# compact.net
KiCad netlist of a schematic drawn in EAGLE
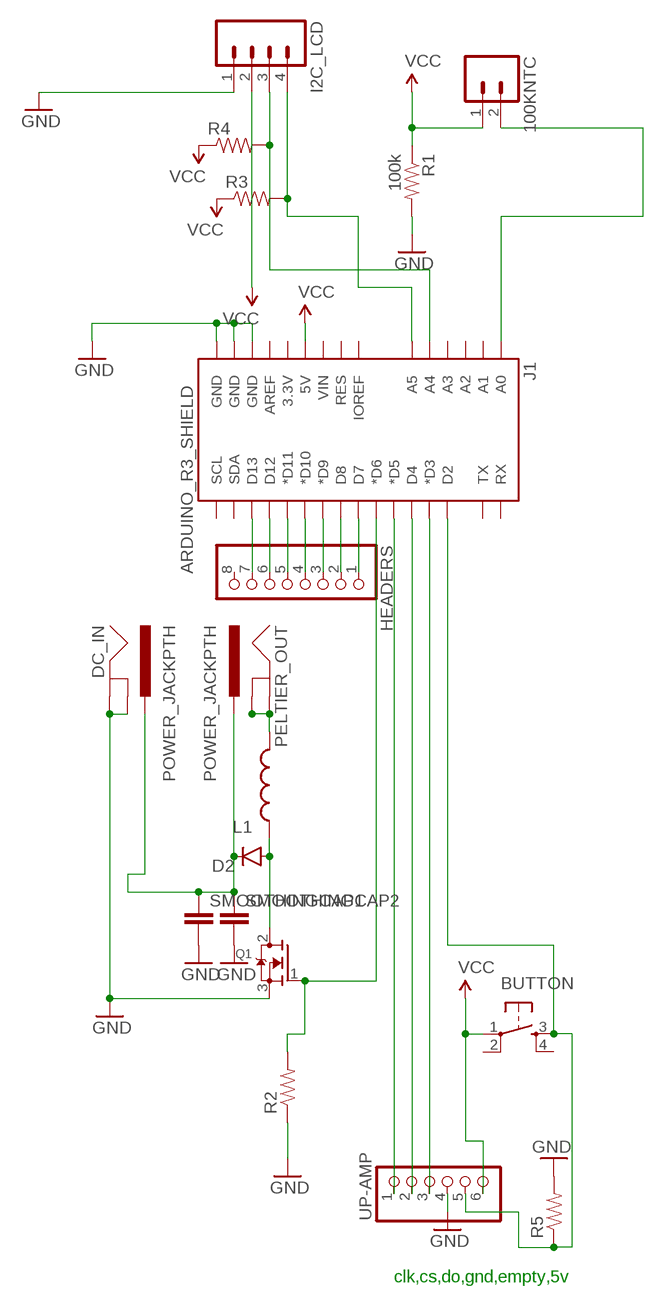
[diagram p0: schematic, sheet 1]

(export (version "E")
  (design (tool "Eeschema 10.0.6"))
  (components
    (comp (ref "100KNTC")
      (value "M02LOCK")
      (footprint "eagle-import:1X02_LOCK")
      (libsource (lib "eagle-import") (part "M02LOCK"))
    )
    (comp (ref "BUTTON")
      (value "TAC_SWITCHPTH")
      (footprint "eagle-import:TACTILE-PTH")
      (libsource (lib "eagle-import") (part "TAC_SWITCHPTH"))
    )
    (comp (ref "D2")
      (value "DIODEPTH")
      (footprint "eagle-import:DIODE-1N4001")
      (libsource (lib "eagle-import") (part "DIODEPTH"))
    )
    (comp (ref "DC_IN")
      (value "POWER_JACKPTH")
      (footprint "eagle-import:POWER_JACK_PTH")
      (libsource (lib "eagle-import") (part "POWER_JACKPTH"))
    )
    (comp (ref "HEADERS")
      (value "PINHD-1X8BIG")
      (footprint "eagle-import:1X08-BIG")
      (libsource (lib "eagle-import") (part "PINHD-1X8BIG"))
    )
    (comp (ref "I2C_LCD")
      (value "M04JST")
      (footprint "eagle-import:1X04-1.5MM_JST")
      (libsource (lib "eagle-import") (part "M04JST"))
    )
    (comp (ref "J1")
      (value "ARDUINO_R3_SHIELD")
      (footprint "eagle-import:UNO_R3_SHIELD")
      (libsource (lib "eagle-import") (part "ARDUINO_R3_SHIELD"))
    )
    (comp (ref "L1")
      (value "INDUCTORRLB0912")
      (footprint "eagle-import:RLB0912")
      (libsource (lib "eagle-import") (part "INDUCTORRLB0912"))
    )
    (comp (ref "PELTIER_OUT")
      (value "POWER_JACKPTH")
      (footprint "eagle-import:POWER_JACK_PTH")
      (libsource (lib "eagle-import") (part "POWER_JACKPTH"))
    )
    (comp (ref "Q1")
      (value "MOSFET-NGDS_TO220V")
      (footprint "eagle-import:TO220V")
      (libsource (lib "eagle-import") (part "MOSFET-NGDS_TO220V"))
    )
    (comp (ref "R1")
      (value "100k")
      (footprint "eagle-import:AXIAL-0.4")
      (libsource (lib "eagle-import") (part "RESISTORPTH-1/4W"))
    )
    (comp (ref "R2")
      (value "RESISTORPTH-1/4W")
      (footprint "eagle-import:AXIAL-0.4")
      (libsource (lib "eagle-import") (part "RESISTORPTH-1/4W"))
    )
    (comp (ref "R3")
      (value "RESISTORPTH-1/4W")
      (footprint "eagle-import:AXIAL-0.4")
      (libsource (lib "eagle-import") (part "SparkFun-Resistors_RESISTORPTH-1/4W"))
    )
    (comp (ref "R4")
      (value "RESISTORPTH-1/4W")
      (footprint "eagle-import:AXIAL-0.4")
      (libsource (lib "eagle-import") (part "SparkFun-Resistors_RESISTORPTH-1/4W"))
    )
    (comp (ref "R5")
      (value "RESISTORPTH-1/4W")
      (footprint "eagle-import:AXIAL-0.4")
      (libsource (lib "eagle-import") (part "RESISTORPTH-1/4W"))
    )
    (comp (ref "SMOOTHINGCAP1")
      (value "CAPPTH3")
      (footprint "eagle-import:CAP-PTH-LARGE")
      (libsource (lib "eagle-import") (part "CAPPTH3"))
    )
    (comp (ref "SMOOTHINGCAP2")
      (value "CAPPTH3")
      (footprint "eagle-import:CAP-PTH-LARGE")
      (libsource (lib "eagle-import") (part "CAPPTH3"))
    )
    (comp (ref "UP-AMP")
      (value "PINHD-1X6")
      (footprint "eagle-import:1X06")
      (libsource (lib "eagle-import") (part "PINHD-1X6"))
    )
  )
  (nets
    (net (code "1") (name "GND") (class "Default")
      (node (ref "DC_IN") (pin "GND") (pinfunction "GND_GND") (pintype "bidirectional"))
      (node (ref "DC_IN") (pin "GNDBREAK") (pinfunction "GNDBREAK_GNDBREAK") (pintype "bidirectional"))
      (node (ref "I2C_LCD") (pin "1") (pinfunction "1_1") (pintype "passive"))
      (node (ref "J1") (pin "GND@0") (pinfunction "GND_GND@0") (pintype "bidirectional"))
      (node (ref "J1") (pin "GND@1") (pinfunction "GND_GND@1") (pintype "bidirectional"))
      (node (ref "J1") (pin "GND@2") (pinfunction "GND_GND@2") (pintype "bidirectional"))
      (node (ref "Q1") (pin "3") (pinfunction "S_3") (pintype "bidirectional"))
      (node (ref "R1") (pin "P$2") (pinfunction "2_P$2") (pintype "passive"))
      (node (ref "R2") (pin "P$1") (pinfunction "1_P$1") (pintype "passive"))
      (node (ref "R5") (pin "P$2") (pinfunction "2_P$2") (pintype "passive"))
      (node (ref "SMOOTHINGCAP1") (pin "2") (pinfunction "2_2") (pintype "passive"))
      (node (ref "SMOOTHINGCAP2") (pin "2") (pinfunction "2_2") (pintype "passive"))
      (node (ref "UP-AMP") (pin "4") (pinfunction "4_4") (pintype "passive"))
    )
    (net (code "2") (name "Net-(100KNTC-Pad2)") (class "Default")
      (node (ref "100KNTC") (pin "2") (pinfunction "2_2") (pintype "passive"))
      (node (ref "J1") (pin "A0") (pinfunction "A0_A0") (pintype "bidirectional"))
    )
    (net (code "3") (name "Net-(D2-PadC)") (class "Default")
      (node (ref "D2") (pin "C") (pinfunction "C_C") (pintype "passive"))
      (node (ref "DC_IN") (pin "PWR") (pinfunction "PWR_PWR") (pintype "bidirectional"))
      (node (ref "PELTIER_OUT") (pin "PWR") (pinfunction "PWR_PWR") (pintype "bidirectional"))
      (node (ref "SMOOTHINGCAP1") (pin "1") (pinfunction "1_1") (pintype "passive"))
      (node (ref "SMOOTHINGCAP2") (pin "1") (pinfunction "1_1") (pintype "passive"))
    )
    (net (code "4") (name "Net-(HEADERS-Pad1)") (class "Default")
      (node (ref "HEADERS") (pin "1") (pinfunction "1_1") (pintype "passive"))
      (node (ref "J1") (pin "D7") (pinfunction "D7_D7") (pintype "bidirectional"))
    )
    (net (code "5") (name "Net-(HEADERS-Pad2)") (class "Default")
      (node (ref "HEADERS") (pin "2") (pinfunction "2_2") (pintype "passive"))
      (node (ref "J1") (pin "D8") (pinfunction "D8_D8") (pintype "bidirectional"))
    )
    (net (code "6") (name "Net-(HEADERS-Pad6)") (class "Default")
      (node (ref "HEADERS") (pin "6") (pinfunction "6_6") (pintype "passive"))
      (node (ref "J1") (pin "D12") (pinfunction "D12_D12") (pintype "bidirectional"))
    )
    (net (code "7") (name "Net-(HEADERS-Pad7)") (class "Default")
      (node (ref "HEADERS") (pin "7") (pinfunction "7_7") (pintype "passive"))
      (node (ref "J1") (pin "D13") (pinfunction "D13_D13") (pintype "bidirectional"))
    )
    (net (code "8") (name "Net-(J1-*D3)") (class "Default")
      (node (ref "J1") (pin "D3") (pinfunction "*D3_D3") (pintype "bidirectional"))
      (node (ref "UP-AMP") (pin "3") (pinfunction "3_3") (pintype "passive"))
    )
    (net (code "9") (name "Net-(J1-*D5)") (class "Default")
      (node (ref "J1") (pin "D5") (pinfunction "*D5_D5") (pintype "bidirectional"))
      (node (ref "UP-AMP") (pin "1") (pinfunction "1_1") (pintype "passive"))
    )
    (net (code "10") (name "Net-(J1-*D6)") (class "Default")
      (node (ref "J1") (pin "D6") (pinfunction "*D6_D6") (pintype "bidirectional"))
      (node (ref "Q1") (pin "1") (pinfunction "G_1") (pintype "bidirectional"))
      (node (ref "R2") (pin "P$2") (pinfunction "2_P$2") (pintype "passive"))
    )
    (net (code "11") (name "Net-(J1-*D9)") (class "Default")
      (node (ref "HEADERS") (pin "3") (pinfunction "3_3") (pintype "passive"))
      (node (ref "J1") (pin "D9") (pinfunction "*D9_D9") (pintype "bidirectional"))
    )
    (net (code "12") (name "Net-(J1-*D10)") (class "Default")
      (node (ref "HEADERS") (pin "4") (pinfunction "4_4") (pintype "passive"))
      (node (ref "J1") (pin "D10") (pinfunction "*D10_D10") (pintype "bidirectional"))
    )
    (net (code "13") (name "Net-(J1-*D11)") (class "Default")
      (node (ref "HEADERS") (pin "5") (pinfunction "5_5") (pintype "passive"))
      (node (ref "J1") (pin "D11") (pinfunction "*D11_D11") (pintype "bidirectional"))
    )
    (net (code "14") (name "Net-(J1-PadD4)") (class "Default")
      (node (ref "J1") (pin "D4") (pinfunction "D4_D4") (pintype "bidirectional"))
      (node (ref "UP-AMP") (pin "2") (pinfunction "2_2") (pintype "passive"))
    )
    (net (code "15") (name "Net-(L1-Pad2)") (class "Default")
      (node (ref "L1") (pin "2") (pinfunction "2_2") (pintype "passive"))
      (node (ref "PELTIER_OUT") (pin "GND") (pinfunction "GND_GND") (pintype "bidirectional"))
      (node (ref "PELTIER_OUT") (pin "GNDBREAK") (pinfunction "GNDBREAK_GNDBREAK") (pintype "bidirectional"))
    )
    (net (code "16") (name "Net-(Q1-D)") (class "Default")
      (node (ref "D2") (pin "A") (pinfunction "A_A") (pintype "passive"))
      (node (ref "L1") (pin "1") (pinfunction "1_1") (pintype "passive"))
      (node (ref "Q1") (pin "2") (pinfunction "D_2") (pintype "bidirectional"))
    )
    (net (code "17") (name "Net-(R3-2)") (class "Default")
      (node (ref "I2C_LCD") (pin "4") (pinfunction "4_4") (pintype "passive"))
      (node (ref "J1") (pin "A5") (pinfunction "A5_A5") (pintype "bidirectional"))
      (node (ref "R3") (pin "P$2") (pinfunction "2_P$2") (pintype "passive"))
    )
    (net (code "18") (name "Net-(R4-2)") (class "Default")
      (node (ref "I2C_LCD") (pin "3") (pinfunction "3_3") (pintype "passive"))
      (node (ref "J1") (pin "A4") (pinfunction "A4_A4") (pintype "bidirectional"))
      (node (ref "R4") (pin "P$2") (pinfunction "2_P$2") (pintype "passive"))
    )
    (net (code "19") (name "Net-(R5-1)") (class "Default")
      (node (ref "BUTTON") (pin "3") (pinfunction "3_3") (pintype "passive"))
      (node (ref "J1") (pin "D2") (pinfunction "D2_D2") (pintype "bidirectional"))
      (node (ref "R5") (pin "P$1") (pinfunction "1_P$1") (pintype "passive"))
      (node (ref "UP-AMP") (pin "5") (pinfunction "5_5") (pintype "passive"))
    )
    (net (code "20") (name "VCC") (class "Default")
      (node (ref "100KNTC") (pin "1") (pinfunction "1_1") (pintype "passive"))
      (node (ref "BUTTON") (pin "1") (pinfunction "1_1") (pintype "passive"))
      (node (ref "I2C_LCD") (pin "2") (pinfunction "2_2") (pintype "passive"))
      (node (ref "J1") (pin "5V") (pinfunction "5V_5V") (pintype "bidirectional"))
      (node (ref "R1") (pin "P$1") (pinfunction "1_P$1") (pintype "passive"))
      (node (ref "R3") (pin "P$1") (pinfunction "1_P$1") (pintype "passive"))
      (node (ref "R4") (pin "P$1") (pinfunction "1_P$1") (pintype "passive"))
      (node (ref "UP-AMP") (pin "6") (pinfunction "6_6") (pintype "passive"))
    )
    (net (code "21") (name "unconnected-(BUTTON-Pad2)") (class "Default")
      (node (ref "BUTTON") (pin "2") (pinfunction "2_2") (pintype "passive"))
    )
    (net (code "22") (name "unconnected-(BUTTON-Pad4)") (class "Default")
      (node (ref "BUTTON") (pin "4") (pinfunction "4_4") (pintype "passive"))
    )
    (net (code "23") (name "unconnected-(HEADERS-Pad8)") (class "Default")
      (node (ref "HEADERS") (pin "8") (pinfunction "8_8") (pintype "passive"))
    )
    (net (code "24") (name "unconnected-(J1-Pad3.3V)") (class "Default")
      (node (ref "J1") (pin "3.3V") (pinfunction "3.3V_3.3V") (pintype "bidirectional"))
    )
    (net (code "25") (name "unconnected-(J1-PadA1)") (class "Default")
      (node (ref "J1") (pin "A1") (pinfunction "A1_A1") (pintype "bidirectional"))
    )
    (net (code "26") (name "unconnected-(J1-PadA2)") (class "Default")
      (node (ref "J1") (pin "A2") (pinfunction "A2_A2") (pintype "bidirectional"))
    )
    (net (code "27") (name "unconnected-(J1-PadA3)") (class "Default")
      (node (ref "J1") (pin "A3") (pinfunction "A3_A3") (pintype "bidirectional"))
    )
    (net (code "28") (name "unconnected-(J1-PadAREF)") (class "Default")
      (node (ref "J1") (pin "AREF") (pinfunction "AREF_AREF") (pintype "bidirectional"))
    )
    (net (code "29") (name "unconnected-(J1-PadIOREF)") (class "Default")
      (node (ref "J1") (pin "IOREF") (pinfunction "IOREF_IOREF") (pintype "bidirectional"))
    )
    (net (code "30") (name "unconnected-(J1-PadRES)") (class "Default")
      (node (ref "J1") (pin "RES") (pinfunction "RES_RES") (pintype "bidirectional"))
    )
    (net (code "31") (name "unconnected-(J1-PadRX)") (class "Default")
      (node (ref "J1") (pin "RX") (pinfunction "RX_RX") (pintype "bidirectional"))
    )
    (net (code "32") (name "unconnected-(J1-PadSCL)") (class "Default")
      (node (ref "J1") (pin "SCL") (pinfunction "SCL_SCL") (pintype "bidirectional"))
    )
    (net (code "33") (name "unconnected-(J1-PadSDA)") (class "Default")
      (node (ref "J1") (pin "SDA") (pinfunction "SDA_SDA") (pintype "bidirectional"))
    )
    (net (code "34") (name "unconnected-(J1-PadTX)") (class "Default")
      (node (ref "J1") (pin "TX") (pinfunction "TX_TX") (pintype "bidirectional"))
    )
    (net (code "35") (name "unconnected-(J1-PadVIN)") (class "Default")
      (node (ref "J1") (pin "VIN") (pinfunction "VIN_VIN") (pintype "bidirectional"))
    )
  )
)
